# kinesis-model-110.net
KiCad netlist of a schematic drawn in EAGLE
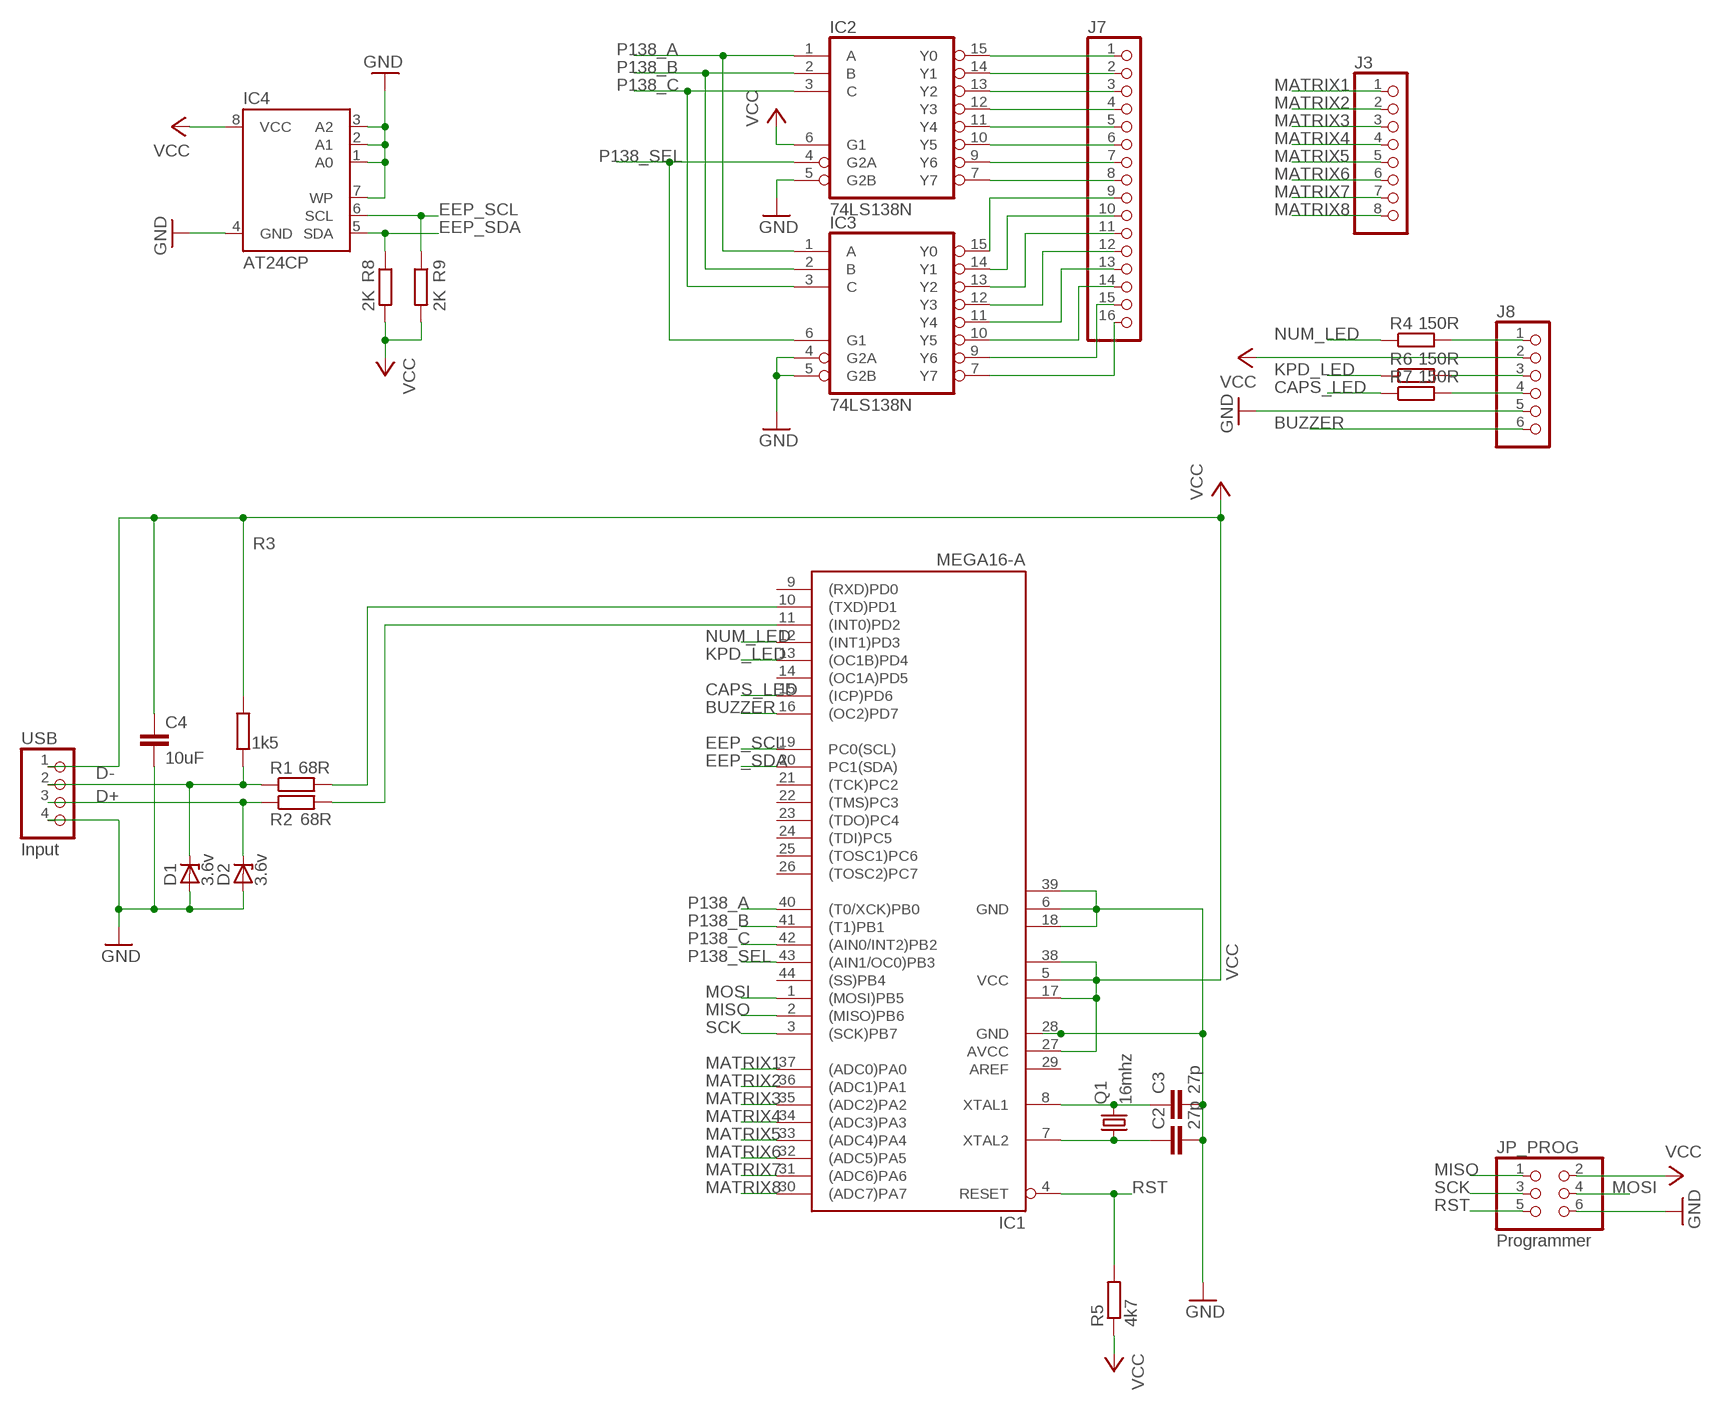
[diagram p0: schematic, sheet 1]

(export (version "E")
  (design (tool "Eeschema 10.0.6"))
  (components
    (comp (ref "C2")
      (value "27p")
      (footprint "eagle-import:C0603")
      (libsource (lib "eagle-import") (part "C-EUC0603"))
    )
    (comp (ref "C3")
      (value "27p")
      (footprint "eagle-import:C0603")
      (libsource (lib "eagle-import") (part "C-EUC0603"))
    )
    (comp (ref "C4")
      (value "10uF")
      (footprint "eagle-import:C0805")
      (libsource (lib "eagle-import") (part "C-EUC0805"))
    )
    (comp (ref "D1")
      (value "3.6v")
      (footprint "eagle-import:SOD80C")
      (libsource (lib "eagle-import") (part "ZENER-DIODESOD80C"))
    )
    (comp (ref "D2")
      (value "3.6v")
      (footprint "eagle-import:SOD80C")
      (libsource (lib "eagle-import") (part "ZENER-DIODESOD80C"))
    )
    (comp (ref "IC1")
      (value "MEGA16-A")
      (footprint "eagle-import:TQFP44")
      (fields (field (name "MPN") "ATMEGA16-16AU"))
      (libsource (lib "eagle-import") (part "MEGA16-A"))
    )
    (comp (ref "IC2")
      (value "74LS138N")
      (footprint "eagle-import:DIL16")
      (libsource (lib "eagle-import") (part "74138NLS"))
    )
    (comp (ref "IC3")
      (value "74LS138N")
      (footprint "eagle-import:DIL16")
      (libsource (lib "eagle-import") (part "74138NLS"))
    )
    (comp (ref "IC4")
      (value "AT24CP")
      (footprint "eagle-import:DIL08")
      (fields (field (name "MPN") "AT24C1024BW-SH-B"))
      (libsource (lib "eagle-import") (part "AT24CP"))
    )
    (comp (ref "J3")
      (value "PINHD-1X8")
      (footprint "eagle-import:1X08")
      (libsource (lib "eagle-import") (part "PINHD-1X8"))
    )
    (comp (ref "J7")
      (value "PINHD-1X16")
      (footprint "eagle-import:1X16")
      (libsource (lib "eagle-import") (part "PINHD-1X16"))
    )
    (comp (ref "J8")
      (value "PINHD-1X6")
      (footprint "eagle-import:1X06")
      (libsource (lib "eagle-import") (part "PINHD-1X6"))
    )
    (comp (ref "JP_PROG")
      (value "Programmer")
      (footprint "eagle-import:2X03")
      (libsource (lib "eagle-import") (part "PINHD-2X3"))
    )
    (comp (ref "Q1")
      (value "16mhz")
      (footprint "eagle-import:HC49_S")
      (libsource (lib "eagle-import") (part "CRYSTALHC49S"))
    )
    (comp (ref "R1")
      (value "68R")
      (footprint "eagle-import:R0603")
      (libsource (lib "eagle-import") (part "R-EU_R0603"))
    )
    (comp (ref "R2")
      (value "68R")
      (footprint "eagle-import:R0603")
      (libsource (lib "eagle-import") (part "R-EU_R0603"))
    )
    (comp (ref "R3")
      (value "1k5")
      (footprint "eagle-import:R0603")
      (libsource (lib "eagle-import") (part "R-EU_R0603"))
    )
    (comp (ref "R4")
      (value "150R")
      (footprint "eagle-import:R0603")
      (libsource (lib "eagle-import") (part "R-EU_R0603"))
    )
    (comp (ref "R5")
      (value "4k7")
      (footprint "eagle-import:R0603")
      (libsource (lib "eagle-import") (part "R-EU_R0603"))
    )
    (comp (ref "R6")
      (value "150R")
      (footprint "eagle-import:R0603")
      (libsource (lib "eagle-import") (part "R-EU_R0603"))
    )
    (comp (ref "R7")
      (value "150R")
      (footprint "eagle-import:R0603")
      (libsource (lib "eagle-import") (part "R-EU_R0603"))
    )
    (comp (ref "R8")
      (value "2K")
      (footprint "eagle-import:R0603")
      (libsource (lib "eagle-import") (part "R-EU_R0603"))
    )
    (comp (ref "R9")
      (value "2K")
      (footprint "eagle-import:R0603")
      (libsource (lib "eagle-import") (part "R-EU_R0603"))
    )
    (comp (ref "USB")
      (value "Input")
      (footprint "eagle-import:1X04")
      (libsource (lib "eagle-import") (part "PINHD-1X4"))
    )
  )
  (nets
    (net (code "1") (name "/BUZZER") (class "Default")
      (node (ref "IC1") (pin "16") (pinfunction "(OC2)PD7_16") (pintype "bidirectional"))
      (node (ref "J8") (pin "6") (pinfunction "6_6") (pintype "passive"))
    )
    (net (code "2") (name "/CAPS_LED") (class "Default")
      (node (ref "IC1") (pin "15") (pinfunction "(ICP)PD6_15") (pintype "bidirectional"))
      (node (ref "R7") (pin "1") (pinfunction "1_1") (pintype "passive"))
    )
    (net (code "3") (name "/D+") (class "Default")
      (node (ref "D2") (pin "C") (pinfunction "C_C") (pintype "passive"))
      (node (ref "R2") (pin "1") (pinfunction "1_1") (pintype "passive"))
      (node (ref "USB") (pin "3") (pinfunction "3_3") (pintype "passive"))
    )
    (net (code "4") (name "/D-") (class "Default")
      (node (ref "D1") (pin "C") (pinfunction "C_C") (pintype "passive"))
      (node (ref "R1") (pin "1") (pinfunction "1_1") (pintype "passive"))
      (node (ref "R3") (pin "1") (pinfunction "1_1") (pintype "passive"))
      (node (ref "USB") (pin "2") (pinfunction "2_2") (pintype "passive"))
    )
    (net (code "5") (name "/EEP_SCL") (class "Default")
      (node (ref "IC1") (pin "19") (pinfunction "PC0(SCL)_19") (pintype "bidirectional"))
      (node (ref "IC4") (pin "6") (pinfunction "SCL_6") (pintype "bidirectional"))
      (node (ref "R9") (pin "1") (pinfunction "1_1") (pintype "passive"))
    )
    (net (code "6") (name "/EEP_SDA") (class "Default")
      (node (ref "IC1") (pin "20") (pinfunction "PC1(SDA)_20") (pintype "bidirectional"))
      (node (ref "IC4") (pin "5") (pinfunction "SDA_5") (pintype "bidirectional"))
      (node (ref "R8") (pin "1") (pinfunction "1_1") (pintype "passive"))
    )
    (net (code "7") (name "/KPD_LED") (class "Default")
      (node (ref "IC1") (pin "13") (pinfunction "(OC1B)PD4_13") (pintype "bidirectional"))
      (node (ref "R6") (pin "1") (pinfunction "1_1") (pintype "passive"))
    )
    (net (code "8") (name "/MATRIX1") (class "Default")
      (node (ref "IC1") (pin "37") (pinfunction "(ADC0)PA0_37") (pintype "bidirectional"))
      (node (ref "J3") (pin "1") (pinfunction "1_1") (pintype "passive"))
    )
    (net (code "9") (name "/MATRIX2") (class "Default")
      (node (ref "IC1") (pin "36") (pinfunction "(ADC1)PA1_36") (pintype "bidirectional"))
      (node (ref "J3") (pin "2") (pinfunction "2_2") (pintype "passive"))
    )
    (net (code "10") (name "/MATRIX3") (class "Default")
      (node (ref "IC1") (pin "35") (pinfunction "(ADC2)PA2_35") (pintype "bidirectional"))
      (node (ref "J3") (pin "3") (pinfunction "3_3") (pintype "passive"))
    )
    (net (code "11") (name "/MATRIX4") (class "Default")
      (node (ref "IC1") (pin "34") (pinfunction "(ADC3)PA3_34") (pintype "bidirectional"))
      (node (ref "J3") (pin "4") (pinfunction "4_4") (pintype "passive"))
    )
    (net (code "12") (name "/MATRIX5") (class "Default")
      (node (ref "IC1") (pin "33") (pinfunction "(ADC4)PA4_33") (pintype "bidirectional"))
      (node (ref "J3") (pin "5") (pinfunction "5_5") (pintype "passive"))
    )
    (net (code "13") (name "/MATRIX6") (class "Default")
      (node (ref "IC1") (pin "32") (pinfunction "(ADC5)PA5_32") (pintype "bidirectional"))
      (node (ref "J3") (pin "6") (pinfunction "6_6") (pintype "passive"))
    )
    (net (code "14") (name "/MATRIX7") (class "Default")
      (node (ref "IC1") (pin "31") (pinfunction "(ADC6)PA6_31") (pintype "bidirectional"))
      (node (ref "J3") (pin "7") (pinfunction "7_7") (pintype "passive"))
    )
    (net (code "15") (name "/MATRIX8") (class "Default")
      (node (ref "IC1") (pin "30") (pinfunction "(ADC7)PA7_30") (pintype "bidirectional"))
      (node (ref "J3") (pin "8") (pinfunction "8_8") (pintype "passive"))
    )
    (net (code "16") (name "/MISO") (class "Default")
      (node (ref "IC1") (pin "2") (pinfunction "(MISO)PB6_2") (pintype "bidirectional"))
      (node (ref "JP_PROG") (pin "1") (pinfunction "1_1") (pintype "passive"))
    )
    (net (code "17") (name "/MOSI") (class "Default")
      (node (ref "IC1") (pin "1") (pinfunction "(MOSI)PB5_1") (pintype "bidirectional"))
      (node (ref "JP_PROG") (pin "4") (pinfunction "4_4") (pintype "passive"))
    )
    (net (code "18") (name "/NUM_LED") (class "Default")
      (node (ref "IC1") (pin "12") (pinfunction "(INT1)PD3_12") (pintype "bidirectional"))
      (node (ref "R4") (pin "1") (pinfunction "1_1") (pintype "passive"))
    )
    (net (code "19") (name "/P138_A") (class "Default")
      (node (ref "IC1") (pin "40") (pinfunction "(T0/XCK)PB0_40") (pintype "bidirectional"))
      (node (ref "IC2") (pin "1") (pinfunction "A_1") (pintype "input"))
      (node (ref "IC3") (pin "1") (pinfunction "A_1") (pintype "input"))
    )
    (net (code "20") (name "/P138_B") (class "Default")
      (node (ref "IC1") (pin "41") (pinfunction "(T1)PB1_41") (pintype "bidirectional"))
      (node (ref "IC2") (pin "2") (pinfunction "B_2") (pintype "input"))
      (node (ref "IC3") (pin "2") (pinfunction "B_2") (pintype "input"))
    )
    (net (code "21") (name "/P138_C") (class "Default")
      (node (ref "IC1") (pin "42") (pinfunction "(AIN0/INT2)PB2_42") (pintype "bidirectional"))
      (node (ref "IC2") (pin "3") (pinfunction "C_3") (pintype "input"))
      (node (ref "IC3") (pin "3") (pinfunction "C_3") (pintype "input"))
    )
    (net (code "22") (name "/P138_SEL") (class "Default")
      (node (ref "IC1") (pin "43") (pinfunction "(AIN1/OC0)PB3_43") (pintype "bidirectional"))
      (node (ref "IC2") (pin "4") (pinfunction "G2A_4") (pintype "input"))
      (node (ref "IC3") (pin "6") (pinfunction "G1_6") (pintype "input"))
    )
    (net (code "23") (name "/RST") (class "Default")
      (node (ref "IC1") (pin "4") (pinfunction "RESET_4") (pintype "input"))
      (node (ref "JP_PROG") (pin "5") (pinfunction "5_5") (pintype "passive"))
      (node (ref "R5") (pin "2") (pinfunction "2_2") (pintype "passive"))
    )
    (net (code "24") (name "/SCK") (class "Default")
      (node (ref "IC1") (pin "3") (pinfunction "(SCK)PB7_3") (pintype "bidirectional"))
      (node (ref "JP_PROG") (pin "3") (pinfunction "3_3") (pintype "passive"))
    )
    (net (code "25") (name "GND") (class "Default")
      (node (ref "C2") (pin "2") (pinfunction "2_2") (pintype "passive"))
      (node (ref "C3") (pin "2") (pinfunction "2_2") (pintype "passive"))
      (node (ref "C4") (pin "2") (pinfunction "2_2") (pintype "passive"))
      (node (ref "D1") (pin "A") (pinfunction "A_A") (pintype "passive"))
      (node (ref "D2") (pin "A") (pinfunction "A_A") (pintype "passive"))
      (node (ref "IC1") (pin "18") (pinfunction "GND1_18") (pintype "power_in"))
      (node (ref "IC1") (pin "28") (pinfunction "GND_28") (pintype "power_in"))
      (node (ref "IC1") (pin "39") (pinfunction "GND2_39") (pintype "power_in"))
      (node (ref "IC1") (pin "6") (pinfunction "GND_6") (pintype "power_in"))
      (node (ref "IC2") (pin "5") (pinfunction "G2B_5") (pintype "input"))
      (node (ref "IC3") (pin "4") (pinfunction "G2A_4") (pintype "input"))
      (node (ref "IC3") (pin "5") (pinfunction "G2B_5") (pintype "input"))
      (node (ref "IC4") (pin "1") (pinfunction "A0_1") (pintype "input"))
      (node (ref "IC4") (pin "2") (pinfunction "A1_2") (pintype "input"))
      (node (ref "IC4") (pin "3") (pinfunction "A2_3") (pintype "input"))
      (node (ref "IC4") (pin "4") (pinfunction "GND_4") (pintype "power_in"))
      (node (ref "IC4") (pin "7") (pinfunction "WP_7") (pintype "input"))
      (node (ref "J8") (pin "5") (pinfunction "5_5") (pintype "passive"))
      (node (ref "JP_PROG") (pin "6") (pinfunction "6_6") (pintype "passive"))
      (node (ref "USB") (pin "4") (pinfunction "4_4") (pintype "passive"))
    )
    (net (code "26") (name "Net-(IC1-(INT0)PD2)") (class "Default")
      (node (ref "IC1") (pin "11") (pinfunction "(INT0)PD2_11") (pintype "bidirectional"))
      (node (ref "R2") (pin "2") (pinfunction "2_2") (pintype "passive"))
    )
    (net (code "27") (name "Net-(IC1-(TXD)PD1)") (class "Default")
      (node (ref "IC1") (pin "10") (pinfunction "(TXD)PD1_10") (pintype "bidirectional"))
      (node (ref "R1") (pin "2") (pinfunction "2_2") (pintype "passive"))
    )
    (net (code "28") (name "Net-(IC1-XTAL1)") (class "Default")
      (node (ref "C3") (pin "1") (pinfunction "1_1") (pintype "passive"))
      (node (ref "IC1") (pin "8") (pinfunction "XTAL1_8") (pintype "bidirectional"))
      (node (ref "Q1") (pin "2") (pinfunction "2_2") (pintype "passive"))
    )
    (net (code "29") (name "Net-(IC1-XTAL2)") (class "Default")
      (node (ref "C2") (pin "1") (pinfunction "1_1") (pintype "passive"))
      (node (ref "IC1") (pin "7") (pinfunction "XTAL2_7") (pintype "bidirectional"))
      (node (ref "Q1") (pin "1") (pinfunction "1_1") (pintype "passive"))
    )
    (net (code "30") (name "Net-(IC2A-Y0)") (class "Default")
      (node (ref "IC2") (pin "15") (pinfunction "Y0_15") (pintype "output"))
      (node (ref "J7") (pin "1") (pinfunction "1_1") (pintype "passive"))
    )
    (net (code "31") (name "Net-(IC2A-Y1)") (class "Default")
      (node (ref "IC2") (pin "14") (pinfunction "Y1_14") (pintype "output"))
      (node (ref "J7") (pin "2") (pinfunction "2_2") (pintype "passive"))
    )
    (net (code "32") (name "Net-(IC2A-Y2)") (class "Default")
      (node (ref "IC2") (pin "13") (pinfunction "Y2_13") (pintype "output"))
      (node (ref "J7") (pin "3") (pinfunction "3_3") (pintype "passive"))
    )
    (net (code "33") (name "Net-(IC2A-Y3)") (class "Default")
      (node (ref "IC2") (pin "12") (pinfunction "Y3_12") (pintype "output"))
      (node (ref "J7") (pin "4") (pinfunction "4_4") (pintype "passive"))
    )
    (net (code "34") (name "Net-(IC2A-Y4)") (class "Default")
      (node (ref "IC2") (pin "11") (pinfunction "Y4_11") (pintype "output"))
      (node (ref "J7") (pin "5") (pinfunction "5_5") (pintype "passive"))
    )
    (net (code "35") (name "Net-(IC2A-Y5)") (class "Default")
      (node (ref "IC2") (pin "10") (pinfunction "Y5_10") (pintype "output"))
      (node (ref "J7") (pin "6") (pinfunction "6_6") (pintype "passive"))
    )
    (net (code "36") (name "Net-(IC2A-Y6)") (class "Default")
      (node (ref "IC2") (pin "9") (pinfunction "Y6_9") (pintype "output"))
      (node (ref "J7") (pin "7") (pinfunction "7_7") (pintype "passive"))
    )
    (net (code "37") (name "Net-(IC2A-Y7)") (class "Default")
      (node (ref "IC2") (pin "7") (pinfunction "Y7_7") (pintype "output"))
      (node (ref "J7") (pin "8") (pinfunction "8_8") (pintype "passive"))
    )
    (net (code "38") (name "Net-(IC3A-Y0)") (class "Default")
      (node (ref "IC3") (pin "15") (pinfunction "Y0_15") (pintype "output"))
      (node (ref "J7") (pin "9") (pinfunction "9_9") (pintype "passive"))
    )
    (net (code "39") (name "Net-(IC3A-Y1)") (class "Default")
      (node (ref "IC3") (pin "14") (pinfunction "Y1_14") (pintype "output"))
      (node (ref "J7") (pin "10") (pinfunction "10_10") (pintype "passive"))
    )
    (net (code "40") (name "Net-(IC3A-Y2)") (class "Default")
      (node (ref "IC3") (pin "13") (pinfunction "Y2_13") (pintype "output"))
      (node (ref "J7") (pin "11") (pinfunction "11_11") (pintype "passive"))
    )
    (net (code "41") (name "Net-(IC3A-Y3)") (class "Default")
      (node (ref "IC3") (pin "12") (pinfunction "Y3_12") (pintype "output"))
      (node (ref "J7") (pin "12") (pinfunction "12_12") (pintype "passive"))
    )
    (net (code "42") (name "Net-(IC3A-Y4)") (class "Default")
      (node (ref "IC3") (pin "11") (pinfunction "Y4_11") (pintype "output"))
      (node (ref "J7") (pin "13") (pinfunction "13_13") (pintype "passive"))
    )
    (net (code "43") (name "Net-(IC3A-Y5)") (class "Default")
      (node (ref "IC3") (pin "10") (pinfunction "Y5_10") (pintype "output"))
      (node (ref "J7") (pin "14") (pinfunction "14_14") (pintype "passive"))
    )
    (net (code "44") (name "Net-(IC3A-Y6)") (class "Default")
      (node (ref "IC3") (pin "9") (pinfunction "Y6_9") (pintype "output"))
      (node (ref "J7") (pin "15") (pinfunction "15_15") (pintype "passive"))
    )
    (net (code "45") (name "Net-(IC3A-Y7)") (class "Default")
      (node (ref "IC3") (pin "7") (pinfunction "Y7_7") (pintype "output"))
      (node (ref "J7") (pin "16") (pinfunction "16_16") (pintype "passive"))
    )
    (net (code "46") (name "Net-(J8-Pad1)") (class "Default")
      (node (ref "J8") (pin "1") (pinfunction "1_1") (pintype "passive"))
      (node (ref "R4") (pin "2") (pinfunction "2_2") (pintype "passive"))
    )
    (net (code "47") (name "Net-(J8-Pad3)") (class "Default")
      (node (ref "J8") (pin "3") (pinfunction "3_3") (pintype "passive"))
      (node (ref "R6") (pin "2") (pinfunction "2_2") (pintype "passive"))
    )
    (net (code "48") (name "Net-(J8-Pad4)") (class "Default")
      (node (ref "J8") (pin "4") (pinfunction "4_4") (pintype "passive"))
      (node (ref "R7") (pin "2") (pinfunction "2_2") (pintype "passive"))
    )
    (net (code "49") (name "VCC") (class "Default")
      (node (ref "C4") (pin "1") (pinfunction "1_1") (pintype "passive"))
      (node (ref "IC1") (pin "17") (pinfunction "VCC1_17") (pintype "power_in"))
      (node (ref "IC1") (pin "27") (pinfunction "AVCC_27") (pintype "power_in"))
      (node (ref "IC1") (pin "38") (pinfunction "VCC2_38") (pintype "power_in"))
      (node (ref "IC1") (pin "5") (pinfunction "VCC_5") (pintype "power_in"))
      (node (ref "IC2") (pin "6") (pinfunction "G1_6") (pintype "input"))
      (node (ref "IC4") (pin "8") (pinfunction "VCC_8") (pintype "power_in"))
      (node (ref "J8") (pin "2") (pinfunction "2_2") (pintype "passive"))
      (node (ref "JP_PROG") (pin "2") (pinfunction "2_2") (pintype "passive"))
      (node (ref "R3") (pin "2") (pinfunction "2_2") (pintype "passive"))
      (node (ref "R5") (pin "1") (pinfunction "1_1") (pintype "passive"))
      (node (ref "R8") (pin "2") (pinfunction "2_2") (pintype "passive"))
      (node (ref "R9") (pin "2") (pinfunction "2_2") (pintype "passive"))
      (node (ref "USB") (pin "1") (pinfunction "1_1") (pintype "passive"))
    )
    (net (code "50") (name "unconnected-(IC1-(OC1A)PD5-Pad14)") (class "Default")
      (node (ref "IC1") (pin "14") (pinfunction "(OC1A)PD5_14") (pintype "bidirectional"))
    )
    (net (code "51") (name "unconnected-(IC1-(RXD)PD0-Pad9)") (class "Default")
      (node (ref "IC1") (pin "9") (pinfunction "(RXD)PD0_9") (pintype "bidirectional"))
    )
    (net (code "52") (name "unconnected-(IC1-(SS)PB4-Pad44)") (class "Default")
      (node (ref "IC1") (pin "44") (pinfunction "(SS)PB4_44") (pintype "bidirectional"))
    )
    (net (code "53") (name "unconnected-(IC1-(TCK)PC2-Pad21)") (class "Default")
      (node (ref "IC1") (pin "21") (pinfunction "(TCK)PC2_21") (pintype "bidirectional"))
    )
    (net (code "54") (name "unconnected-(IC1-(TDI)PC5-Pad24)") (class "Default")
      (node (ref "IC1") (pin "24") (pinfunction "(TDI)PC5_24") (pintype "bidirectional"))
    )
    (net (code "55") (name "unconnected-(IC1-(TDO)PC4-Pad23)") (class "Default")
      (node (ref "IC1") (pin "23") (pinfunction "(TDO)PC4_23") (pintype "bidirectional"))
    )
    (net (code "56") (name "unconnected-(IC1-(TMS)PC3-Pad22)") (class "Default")
      (node (ref "IC1") (pin "22") (pinfunction "(TMS)PC3_22") (pintype "bidirectional"))
    )
    (net (code "57") (name "unconnected-(IC1-(TOSC1)PC6-Pad25)") (class "Default")
      (node (ref "IC1") (pin "25") (pinfunction "(TOSC1)PC6_25") (pintype "bidirectional"))
    )
    (net (code "58") (name "unconnected-(IC1-(TOSC2)PC7-Pad26)") (class "Default")
      (node (ref "IC1") (pin "26") (pinfunction "(TOSC2)PC7_26") (pintype "bidirectional"))
    )
    (net (code "59") (name "unconnected-(IC1-AREF-Pad29)") (class "Default")
      (node (ref "IC1") (pin "29") (pinfunction "AREF_29") (pintype "passive"))
    )
  )
)
